# vco-4069-schmitz-smt.net
KiCad netlist of a schematic drawn in EAGLE
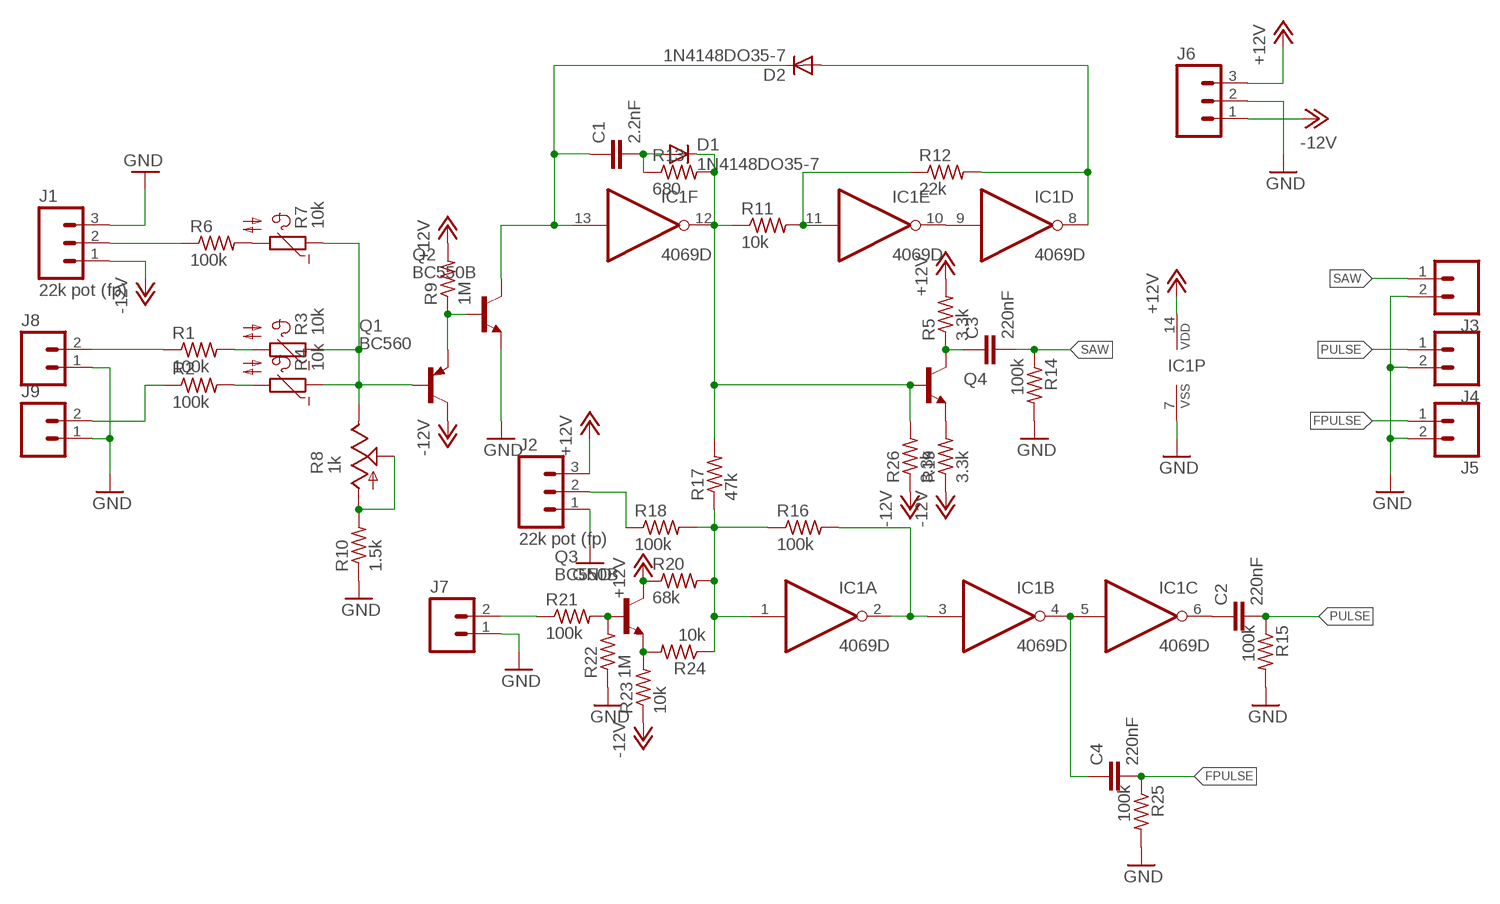
[diagram p0: schematic, sheet 1]

(export (version "E")
  (design (tool "Eeschema 10.0.6"))
  (components
    (comp (ref "C1")
      (value "2.2nF")
      (footprint "eagle-import:C0805")
      (libsource (lib "eagle-import") (part "C-EUC0805"))
    )
    (comp (ref "C2")
      (value "220nF")
      (footprint "eagle-import:C0805")
      (libsource (lib "eagle-import") (part "C-EUC0805"))
    )
    (comp (ref "C3")
      (value "220nF")
      (footprint "eagle-import:C0805")
      (libsource (lib "eagle-import") (part "C-EUC0805"))
    )
    (comp (ref "C4")
      (value "220nF")
      (footprint "eagle-import:C0805")
      (libsource (lib "eagle-import") (part "C-EUC0805"))
    )
    (comp (ref "D1")
      (value "1N4148DO35-7")
      (footprint "eagle-import:DO35-7")
      (libsource (lib "eagle-import") (part "1N4148DO35-7"))
    )
    (comp (ref "D2")
      (value "1N4148DO35-7")
      (footprint "eagle-import:DO35-7")
      (libsource (lib "eagle-import") (part "1N4148DO35-7"))
    )
    (comp (ref "IC1")
      (value "4069D")
      (footprint "eagle-import:SO14")
      (libsource (lib "eagle-import") (part "4069D"))
    )
    (comp (ref "J1")
      (value "22k pot (fp)")
      (footprint "eagle-import:1X03")
      (libsource (lib "eagle-import") (part "M03PTH"))
    )
    (comp (ref "J2")
      (value "22k pot (fp)")
      (footprint "eagle-import:1X03")
      (libsource (lib "eagle-import") (part "M03PTH"))
    )
    (comp (ref "J3")
      (value "M02PTH")
      (footprint "eagle-import:1X02")
      (libsource (lib "eagle-import") (part "M02PTH"))
    )
    (comp (ref "J4")
      (value "M02PTH")
      (footprint "eagle-import:1X02")
      (libsource (lib "eagle-import") (part "M02PTH"))
    )
    (comp (ref "J5")
      (value "M02PTH")
      (footprint "eagle-import:1X02")
      (libsource (lib "eagle-import") (part "M02PTH"))
    )
    (comp (ref "J6")
      (value "M03PTH")
      (footprint "eagle-import:1X03")
      (libsource (lib "eagle-import") (part "M03PTH"))
    )
    (comp (ref "J7")
      (value "M02PTH")
      (footprint "eagle-import:1X02")
      (libsource (lib "eagle-import") (part "M02PTH"))
    )
    (comp (ref "J8")
      (value "M02PTH")
      (footprint "eagle-import:1X02")
      (libsource (lib "eagle-import") (part "M02PTH"))
    )
    (comp (ref "J9")
      (value "M02PTH")
      (footprint "eagle-import:1X02")
      (libsource (lib "eagle-import") (part "M02PTH"))
    )
    (comp (ref "Q1")
      (value "BC560")
      (footprint "eagle-import:TO92-EBC")
      (libsource (lib "eagle-import") (part "BC560"))
    )
    (comp (ref "Q2")
      (value "BC550B")
      (footprint "eagle-import:TO92-EBC")
      (libsource (lib "eagle-import") (part "BC550B"))
    )
    (comp (ref "Q3")
      (value "BC550B")
      (footprint "eagle-import:TO92-EBC")
      (libsource (lib "eagle-import") (part "BC550B"))
    )
    (comp (ref "Q4")
      (value "TRANSISTOR_NPNMMBT2222A")
      (footprint "eagle-import:SOT23-3")
      (libsource (lib "eagle-import") (part "TRANSISTOR_NPNMMBT2222A"))
    )
    (comp (ref "R1")
      (value "100k")
      (footprint "eagle-import:R0805")
      (libsource (lib "eagle-import") (part "R-US_R0805"))
    )
    (comp (ref "R2")
      (value "100k")
      (footprint "eagle-import:R0805")
      (libsource (lib "eagle-import") (part "R-US_R0805"))
    )
    (comp (ref "R3")
      (value "10k")
      (footprint "eagle-import:N640")
      (libsource (lib "eagle-import") (part "NTC640-9"))
    )
    (comp (ref "R4")
      (value "10k")
      (footprint "eagle-import:N640")
      (libsource (lib "eagle-import") (part "NTC640-9"))
    )
    (comp (ref "R5")
      (value "3.3k")
      (footprint "eagle-import:R0805")
      (libsource (lib "eagle-import") (part "R-US_R0805"))
    )
    (comp (ref "R6")
      (value "100k")
      (footprint "eagle-import:R0805")
      (libsource (lib "eagle-import") (part "R-US_R0805"))
    )
    (comp (ref "R7")
      (value "10k")
      (footprint "eagle-import:N640")
      (libsource (lib "eagle-import") (part "NTC640-9"))
    )
    (comp (ref "R8")
      (value "1k")
      (footprint "eagle-import:B25P")
      (libsource (lib "eagle-import") (part "TRIM_US-B25P"))
    )
    (comp (ref "R9")
      (value "1M")
      (footprint "eagle-import:R0805")
      (libsource (lib "eagle-import") (part "R-US_R0805"))
    )
    (comp (ref "R10")
      (value "1.5k")
      (footprint "eagle-import:R0805")
      (libsource (lib "eagle-import") (part "R-US_R0805"))
    )
    (comp (ref "R11")
      (value "10k")
      (footprint "eagle-import:R0805")
      (libsource (lib "eagle-import") (part "R-US_R0805"))
    )
    (comp (ref "R12")
      (value "22k")
      (footprint "eagle-import:R0805")
      (libsource (lib "eagle-import") (part "R-US_R0805"))
    )
    (comp (ref "R13")
      (value "680")
      (footprint "eagle-import:R0805")
      (libsource (lib "eagle-import") (part "R-US_R0805"))
    )
    (comp (ref "R14")
      (value "100k")
      (footprint "eagle-import:R0805")
      (libsource (lib "eagle-import") (part "R-US_R0805"))
    )
    (comp (ref "R15")
      (value "100k")
      (footprint "eagle-import:R0805")
      (libsource (lib "eagle-import") (part "R-US_R0805"))
    )
    (comp (ref "R16")
      (value "100k")
      (footprint "eagle-import:R0805")
      (libsource (lib "eagle-import") (part "R-US_R0805"))
    )
    (comp (ref "R17")
      (value "47k")
      (footprint "eagle-import:R0805")
      (libsource (lib "eagle-import") (part "R-US_R0805"))
    )
    (comp (ref "R18")
      (value "100k")
      (footprint "eagle-import:R0805")
      (libsource (lib "eagle-import") (part "R-US_R0805"))
    )
    (comp (ref "R19")
      (value "3.3k")
      (footprint "eagle-import:R0805")
      (libsource (lib "eagle-import") (part "R-US_R0805"))
    )
    (comp (ref "R20")
      (value "68k")
      (footprint "eagle-import:R0805")
      (libsource (lib "eagle-import") (part "R-US_R0805"))
    )
    (comp (ref "R21")
      (value "100k")
      (footprint "eagle-import:R0805")
      (libsource (lib "eagle-import") (part "R-US_R0805"))
    )
    (comp (ref "R22")
      (value "1M")
      (footprint "eagle-import:R0805")
      (libsource (lib "eagle-import") (part "R-US_R0805"))
    )
    (comp (ref "R23")
      (value "10k")
      (footprint "eagle-import:R0805")
      (libsource (lib "eagle-import") (part "R-US_R0805"))
    )
    (comp (ref "R24")
      (value "10k")
      (footprint "eagle-import:R0805")
      (libsource (lib "eagle-import") (part "R-US_R0805"))
    )
    (comp (ref "R25")
      (value "100k")
      (footprint "eagle-import:R0805")
      (libsource (lib "eagle-import") (part "R-US_R0805"))
    )
    (comp (ref "R26")
      (value "3.3k")
      (footprint "eagle-import:R0805")
      (libsource (lib "eagle-import") (part "R-US_R0805"))
    )
  )
  (nets
    (net (code "1") (name "+12V") (class "Default")
      (node (ref "IC1") (pin "14") (pinfunction "VDD_14") (pintype "power_in"))
      (node (ref "J2") (pin "3") (pinfunction "3_3") (pintype "passive"))
      (node (ref "J6") (pin "3") (pinfunction "3_3") (pintype "passive"))
      (node (ref "Q3") (pin "C") (pinfunction "C_C") (pintype "passive"))
      (node (ref "R20") (pin "1") (pinfunction "1_1") (pintype "passive"))
      (node (ref "R5") (pin "2") (pinfunction "2_2") (pintype "passive"))
      (node (ref "R9") (pin "2") (pinfunction "2_2") (pintype "passive"))
    )
    (net (code "2") (name "-12V") (class "Default")
      (node (ref "J1") (pin "1") (pinfunction "1_1") (pintype "passive"))
      (node (ref "J6") (pin "1") (pinfunction "1_1") (pintype "passive"))
      (node (ref "Q1") (pin "C") (pinfunction "C_C") (pintype "passive"))
      (node (ref "R19") (pin "1") (pinfunction "1_1") (pintype "passive"))
      (node (ref "R23") (pin "1") (pinfunction "1_1") (pintype "passive"))
      (node (ref "R26") (pin "1") (pinfunction "1_1") (pintype "passive"))
    )
    (net (code "3") (name "FPULSE") (class "Default")
      (node (ref "C4") (pin "2") (pinfunction "2_2") (pintype "passive"))
      (node (ref "J5") (pin "1") (pinfunction "1_1") (pintype "passive"))
      (node (ref "R25") (pin "1") (pinfunction "1_1") (pintype "passive"))
    )
    (net (code "4") (name "GND") (class "Default")
      (node (ref "IC1") (pin "7") (pinfunction "VSS_7") (pintype "power_in"))
      (node (ref "J1") (pin "3") (pinfunction "3_3") (pintype "passive"))
      (node (ref "J2") (pin "1") (pinfunction "1_1") (pintype "passive"))
      (node (ref "J3") (pin "2") (pinfunction "2_2") (pintype "passive"))
      (node (ref "J4") (pin "2") (pinfunction "2_2") (pintype "passive"))
      (node (ref "J5") (pin "2") (pinfunction "2_2") (pintype "passive"))
      (node (ref "J6") (pin "2") (pinfunction "2_2") (pintype "passive"))
      (node (ref "J7") (pin "1") (pinfunction "1_1") (pintype "passive"))
      (node (ref "J8") (pin "1") (pinfunction "1_1") (pintype "passive"))
      (node (ref "J9") (pin "1") (pinfunction "1_1") (pintype "passive"))
      (node (ref "Q2") (pin "E") (pinfunction "E_E") (pintype "passive"))
      (node (ref "R10") (pin "1") (pinfunction "1_1") (pintype "passive"))
      (node (ref "R14") (pin "2") (pinfunction "2_2") (pintype "passive"))
      (node (ref "R15") (pin "2") (pinfunction "2_2") (pintype "passive"))
      (node (ref "R22") (pin "1") (pinfunction "1_1") (pintype "passive"))
      (node (ref "R25") (pin "2") (pinfunction "2_2") (pintype "passive"))
    )
    (net (code "5") (name "Net-(C1-Pad2)") (class "Default")
      (node (ref "C1") (pin "2") (pinfunction "2_2") (pintype "passive"))
      (node (ref "D1") (pin "A") (pinfunction "A_A") (pintype "passive"))
      (node (ref "R13") (pin "1") (pinfunction "1_1") (pintype "passive"))
    )
    (net (code "6") (name "Net-(IC1A-I)") (class "Default")
      (node (ref "IC1") (pin "1") (pinfunction "I_1") (pintype "input"))
      (node (ref "R16") (pin "1") (pinfunction "1_1") (pintype "passive"))
      (node (ref "R17") (pin "1") (pinfunction "1_1") (pintype "passive"))
      (node (ref "R18") (pin "2") (pinfunction "2_2") (pintype "passive"))
      (node (ref "R20") (pin "2") (pinfunction "2_2") (pintype "passive"))
      (node (ref "R24") (pin "1") (pinfunction "1_1") (pintype "passive"))
    )
    (net (code "7") (name "Net-(IC1A-O)") (class "Default")
      (node (ref "IC1") (pin "2") (pinfunction "O_2") (pintype "output"))
      (node (ref "IC1") (pin "3") (pinfunction "I_3") (pintype "input"))
      (node (ref "R16") (pin "2") (pinfunction "2_2") (pintype "passive"))
    )
    (net (code "8") (name "Net-(IC1B-O)") (class "Default")
      (node (ref "C4") (pin "1") (pinfunction "1_1") (pintype "passive"))
      (node (ref "IC1") (pin "4") (pinfunction "O_4") (pintype "output"))
      (node (ref "IC1") (pin "5") (pinfunction "I_5") (pintype "input"))
    )
    (net (code "9") (name "Net-(IC1C-O)") (class "Default")
      (node (ref "C2") (pin "1") (pinfunction "1_1") (pintype "passive"))
      (node (ref "IC1") (pin "6") (pinfunction "O_6") (pintype "output"))
    )
    (net (code "10") (name "Net-(IC1D-I)") (class "Default")
      (node (ref "IC1") (pin "10") (pinfunction "O_10") (pintype "output"))
      (node (ref "IC1") (pin "9") (pinfunction "I_9") (pintype "input"))
    )
    (net (code "11") (name "Net-(IC1D-O)") (class "Default")
      (node (ref "D2") (pin "A") (pinfunction "A_A") (pintype "passive"))
      (node (ref "IC1") (pin "8") (pinfunction "O_8") (pintype "output"))
      (node (ref "R12") (pin "2") (pinfunction "2_2") (pintype "passive"))
    )
    (net (code "12") (name "Net-(IC1E-I)") (class "Default")
      (node (ref "IC1") (pin "11") (pinfunction "I_11") (pintype "input"))
      (node (ref "R11") (pin "2") (pinfunction "2_2") (pintype "passive"))
      (node (ref "R12") (pin "1") (pinfunction "1_1") (pintype "passive"))
    )
    (net (code "13") (name "Net-(IC1F-I)") (class "Default")
      (node (ref "C1") (pin "1") (pinfunction "1_1") (pintype "passive"))
      (node (ref "D2") (pin "C") (pinfunction "C_C") (pintype "passive"))
      (node (ref "IC1") (pin "13") (pinfunction "I_13") (pintype "input"))
      (node (ref "Q2") (pin "C") (pinfunction "C_C") (pintype "passive"))
    )
    (net (code "14") (name "Net-(IC1F-O)") (class "Default")
      (node (ref "D1") (pin "C") (pinfunction "C_C") (pintype "passive"))
      (node (ref "IC1") (pin "12") (pinfunction "O_12") (pintype "output"))
      (node (ref "Q4") (pin "1") (pinfunction "B_1") (pintype "passive"))
      (node (ref "R11") (pin "1") (pinfunction "1_1") (pintype "passive"))
      (node (ref "R13") (pin "2") (pinfunction "2_2") (pintype "passive"))
      (node (ref "R17") (pin "2") (pinfunction "2_2") (pintype "passive"))
      (node (ref "R26") (pin "2") (pinfunction "2_2") (pintype "passive"))
    )
    (net (code "15") (name "Net-(J1-Pad2)") (class "Default")
      (node (ref "J1") (pin "2") (pinfunction "2_2") (pintype "passive"))
      (node (ref "R6") (pin "1") (pinfunction "1_1") (pintype "passive"))
    )
    (net (code "16") (name "Net-(J2-Pad2)") (class "Default")
      (node (ref "J2") (pin "2") (pinfunction "2_2") (pintype "passive"))
      (node (ref "R18") (pin "1") (pinfunction "1_1") (pintype "passive"))
    )
    (net (code "17") (name "Net-(J7-Pad2)") (class "Default")
      (node (ref "J7") (pin "2") (pinfunction "2_2") (pintype "passive"))
      (node (ref "R21") (pin "1") (pinfunction "1_1") (pintype "passive"))
    )
    (net (code "18") (name "Net-(J8-Pad2)") (class "Default")
      (node (ref "J8") (pin "2") (pinfunction "2_2") (pintype "passive"))
      (node (ref "R1") (pin "1") (pinfunction "1_1") (pintype "passive"))
    )
    (net (code "19") (name "Net-(J9-Pad2)") (class "Default")
      (node (ref "J9") (pin "2") (pinfunction "2_2") (pintype "passive"))
      (node (ref "R2") (pin "1") (pinfunction "1_1") (pintype "passive"))
    )
    (net (code "20") (name "Net-(Q1-PadB)") (class "Default")
      (node (ref "Q1") (pin "B") (pinfunction "B_B") (pintype "passive"))
      (node (ref "R3") (pin "1") (pinfunction "1_1") (pintype "passive"))
      (node (ref "R4") (pin "1") (pinfunction "1_1") (pintype "passive"))
      (node (ref "R7") (pin "1") (pinfunction "1_1") (pintype "passive"))
      (node (ref "R8") (pin "E") (pinfunction "E_E") (pintype "passive"))
    )
    (net (code "21") (name "Net-(Q1-PadE)") (class "Default")
      (node (ref "Q1") (pin "E") (pinfunction "E_E") (pintype "passive"))
      (node (ref "Q2") (pin "B") (pinfunction "B_B") (pintype "passive"))
      (node (ref "R9") (pin "1") (pinfunction "1_1") (pintype "passive"))
    )
    (net (code "22") (name "Net-(Q3-PadB)") (class "Default")
      (node (ref "Q3") (pin "B") (pinfunction "B_B") (pintype "passive"))
      (node (ref "R21") (pin "2") (pinfunction "2_2") (pintype "passive"))
      (node (ref "R22") (pin "2") (pinfunction "2_2") (pintype "passive"))
    )
    (net (code "23") (name "Net-(Q3-PadE)") (class "Default")
      (node (ref "Q3") (pin "E") (pinfunction "E_E") (pintype "passive"))
      (node (ref "R23") (pin "2") (pinfunction "2_2") (pintype "passive"))
      (node (ref "R24") (pin "2") (pinfunction "2_2") (pintype "passive"))
    )
    (net (code "24") (name "Net-(Q4-C)") (class "Default")
      (node (ref "C3") (pin "1") (pinfunction "1_1") (pintype "passive"))
      (node (ref "Q4") (pin "3") (pinfunction "C_3") (pintype "passive"))
      (node (ref "R5") (pin "1") (pinfunction "1_1") (pintype "passive"))
    )
    (net (code "25") (name "Net-(Q4-E)") (class "Default")
      (node (ref "Q4") (pin "2") (pinfunction "E_2") (pintype "passive"))
      (node (ref "R19") (pin "2") (pinfunction "2_2") (pintype "passive"))
    )
    (net (code "26") (name "Net-(R1-Pad2)") (class "Default")
      (node (ref "R1") (pin "2") (pinfunction "2_2") (pintype "passive"))
      (node (ref "R3") (pin "2") (pinfunction "2_2") (pintype "passive"))
    )
    (net (code "27") (name "Net-(R2-Pad2)") (class "Default")
      (node (ref "R2") (pin "2") (pinfunction "2_2") (pintype "passive"))
      (node (ref "R4") (pin "2") (pinfunction "2_2") (pintype "passive"))
    )
    (net (code "28") (name "Net-(R6-Pad2)") (class "Default")
      (node (ref "R6") (pin "2") (pinfunction "2_2") (pintype "passive"))
      (node (ref "R7") (pin "2") (pinfunction "2_2") (pintype "passive"))
    )
    (net (code "29") (name "Net-(R10-Pad2)") (class "Default")
      (node (ref "R10") (pin "2") (pinfunction "2_2") (pintype "passive"))
      (node (ref "R8") (pin "A") (pinfunction "A_A") (pintype "passive"))
      (node (ref "R8") (pin "S") (pinfunction "S_S") (pintype "passive"))
    )
    (net (code "30") (name "PULSE") (class "Default")
      (node (ref "C2") (pin "2") (pinfunction "2_2") (pintype "passive"))
      (node (ref "J4") (pin "1") (pinfunction "1_1") (pintype "passive"))
      (node (ref "R15") (pin "1") (pinfunction "1_1") (pintype "passive"))
    )
    (net (code "31") (name "SAW") (class "Default")
      (node (ref "C3") (pin "2") (pinfunction "2_2") (pintype "passive"))
      (node (ref "J3") (pin "1") (pinfunction "1_1") (pintype "passive"))
      (node (ref "R14") (pin "1") (pinfunction "1_1") (pintype "passive"))
    )
  )
)
